# Final_Design.net
KiCad netlist of a schematic drawn in Altium Designer
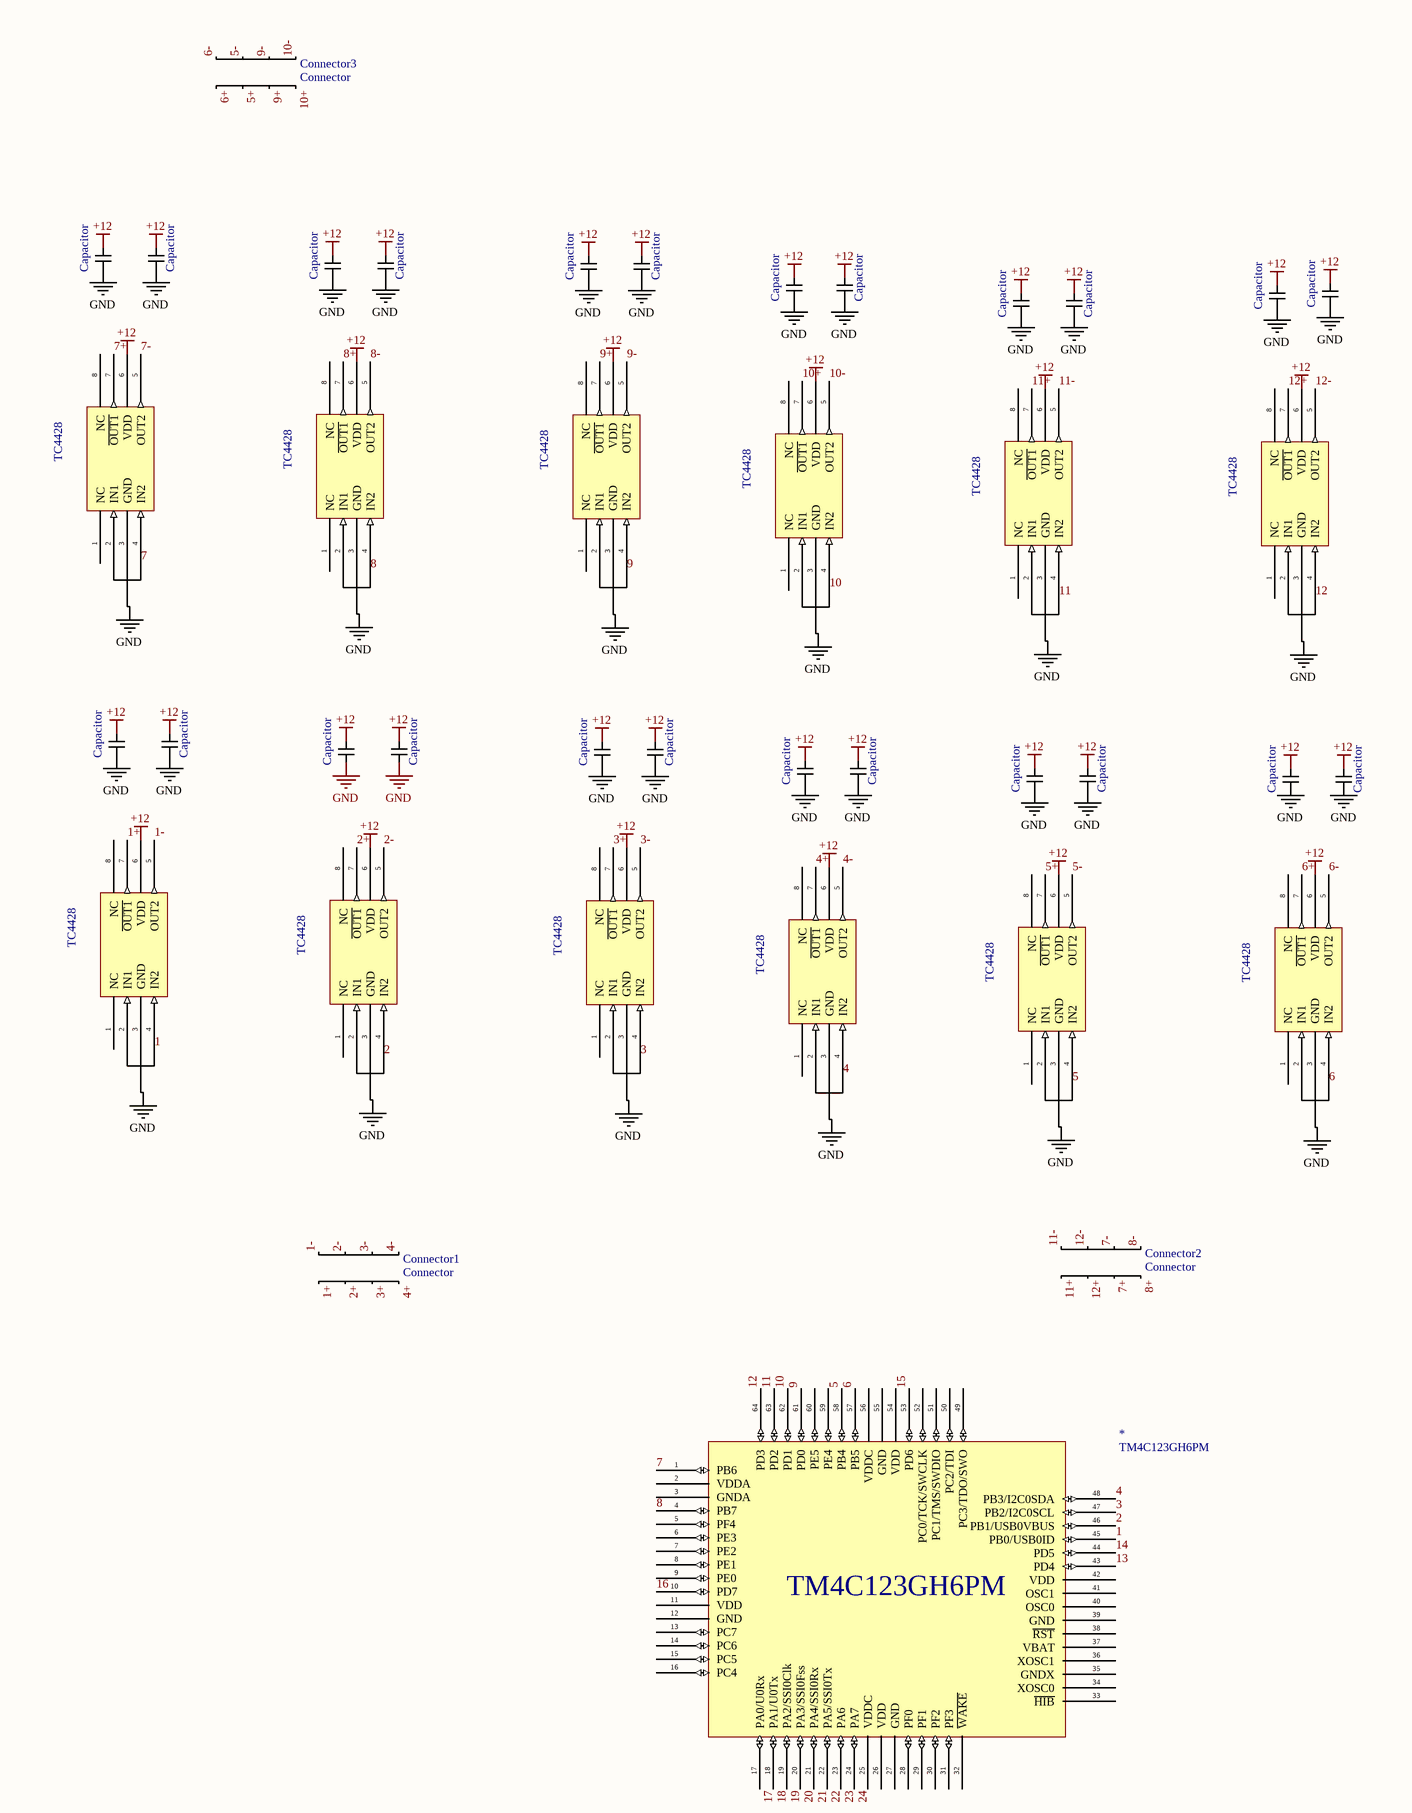
[diagram p0: Final Design.SchDoc, top]
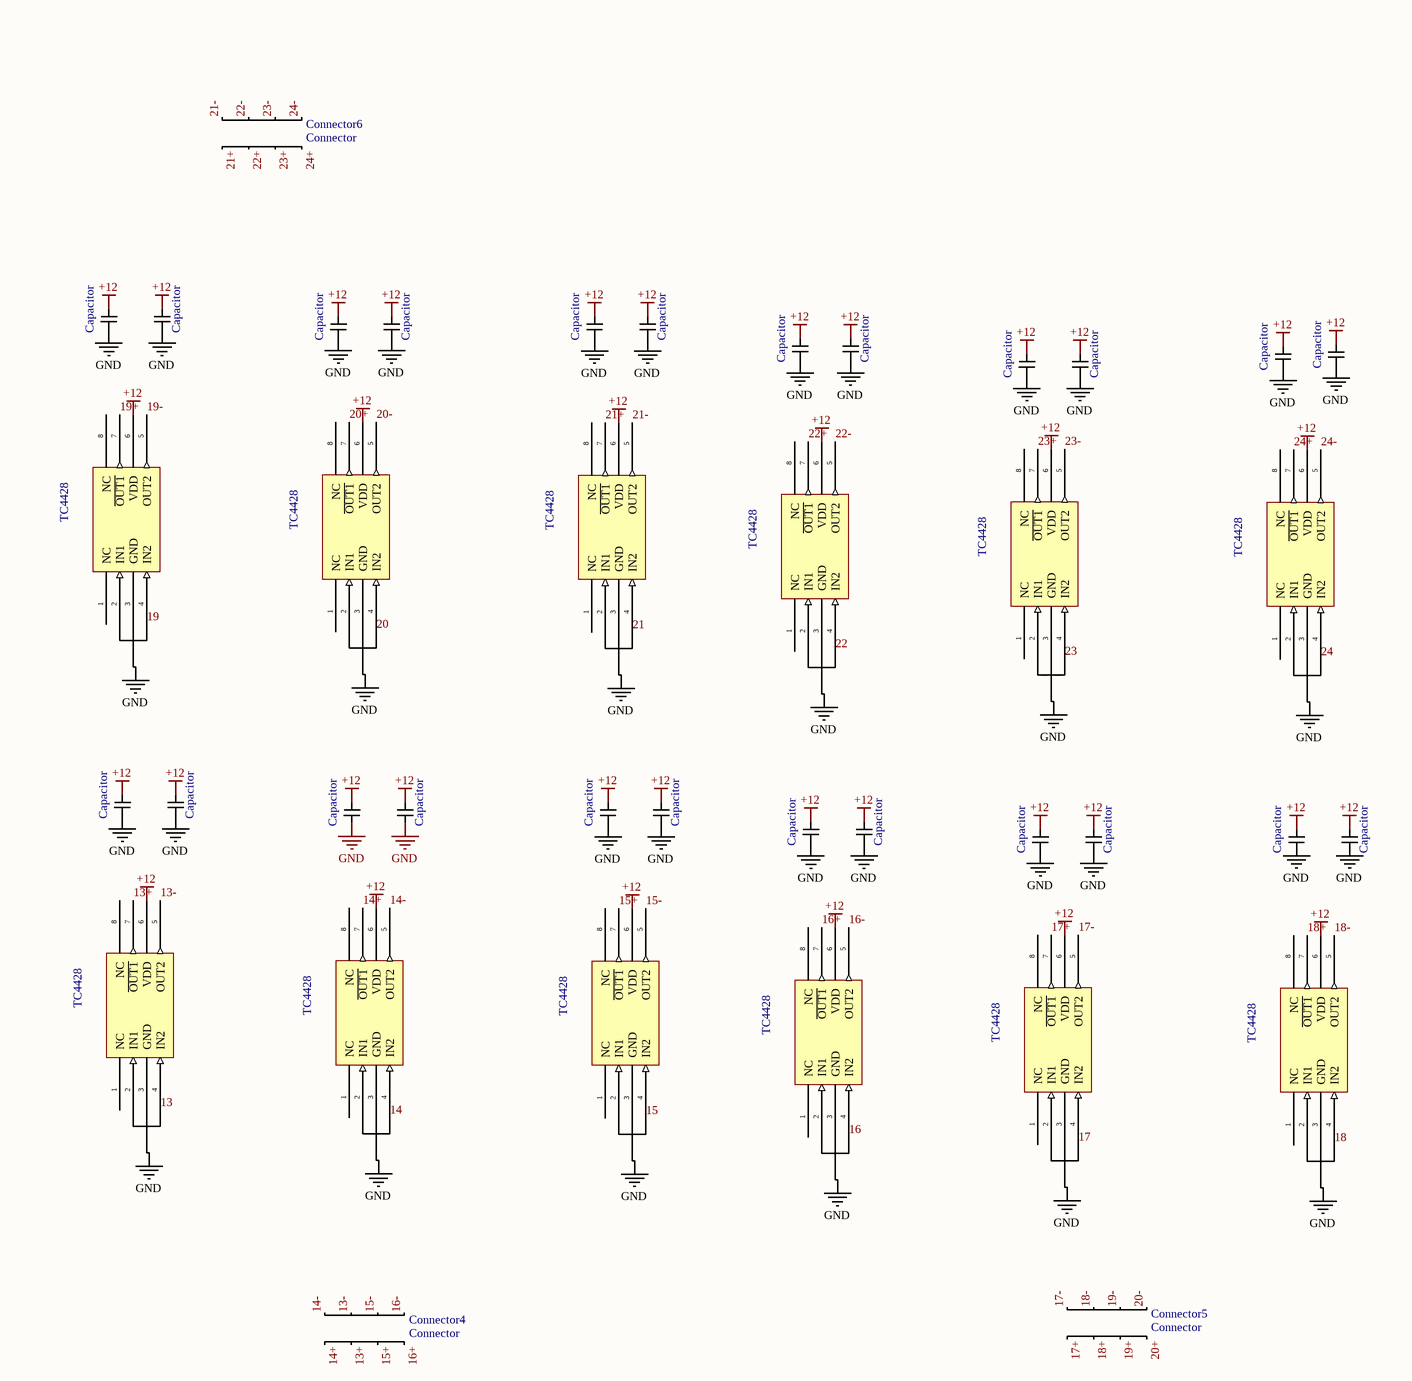
[diagram p1: Final Design.SchDoc, bottom]

(export (version "E")
  (design (tool "Eeschema 10.0.6"))
  (components
    (comp (ref "*")
      (value "TM4C123GH6PM")
      (footprint "TM4C123")
      (description "IC MCU 32BIT 256KB FLASH 64LQFP")
      (libsource (lib "Schlib1") (part "TM4C123GH6PM"))
    )
    (comp (ref "1")
      (value "TC4428")
      (footprint "TC4428")
      (description "Dual High-Speed Power MOSFET Drivers")
      (libsource (lib "Schlib1") (part "TC4428"))
    )
    (comp (ref "1.1")
      (value "Capacitor")
      (footprint "Chip2PinSM127P600-8N")
      (libsource (lib "Schlib1") (part "Capacitor"))
    )
    (comp (ref "1.2")
      (value "Capacitor")
      (footprint "Chip2PinSM127P600-8N")
      (libsource (lib "Schlib1") (part "Capacitor"))
    )
    (comp (ref "2")
      (value "TC4428")
      (footprint "TC4428")
      (description "Dual High-Speed Power MOSFET Drivers")
      (libsource (lib "Schlib1") (part "TC4428"))
    )
    (comp (ref "2.1")
      (value "Capacitor")
      (footprint "Chip2PinSM127P600-8N")
      (libsource (lib "Schlib1") (part "Capacitor"))
    )
    (comp (ref "2.2")
      (value "Capacitor")
      (footprint "Chip2PinSM127P600-8N")
      (libsource (lib "Schlib1") (part "Capacitor"))
    )
    (comp (ref "3")
      (value "TC4428")
      (footprint "TC4428")
      (description "Dual High-Speed Power MOSFET Drivers")
      (libsource (lib "Schlib1") (part "TC4428"))
    )
    (comp (ref "3.1")
      (value "Capacitor")
      (footprint "Chip2PinSM127P600-8N")
      (libsource (lib "Schlib1") (part "Capacitor"))
    )
    (comp (ref "3.2")
      (value "Capacitor")
      (footprint "Chip2PinSM127P600-8N")
      (libsource (lib "Schlib1") (part "Capacitor"))
    )
    (comp (ref "4")
      (value "TC4428")
      (footprint "TC4428")
      (description "Dual High-Speed Power MOSFET Drivers")
      (libsource (lib "Schlib1") (part "TC4428"))
    )
    (comp (ref "4.1")
      (value "Capacitor")
      (footprint "Chip2PinSM127P600-8N")
      (libsource (lib "Schlib1") (part "Capacitor"))
    )
    (comp (ref "4.2")
      (value "Capacitor")
      (footprint "Chip2PinSM127P600-8N")
      (libsource (lib "Schlib1") (part "Capacitor"))
    )
    (comp (ref "5")
      (value "TC4428")
      (footprint "TC4428")
      (description "Dual High-Speed Power MOSFET Drivers")
      (libsource (lib "Schlib1") (part "TC4428"))
    )
    (comp (ref "5.1")
      (value "Capacitor")
      (footprint "Chip2PinSM127P600-8N")
      (libsource (lib "Schlib1") (part "Capacitor"))
    )
    (comp (ref "5.2")
      (value "Capacitor")
      (footprint "Chip2PinSM127P600-8N")
      (libsource (lib "Schlib1") (part "Capacitor"))
    )
    (comp (ref "6")
      (value "TC4428")
      (footprint "TC4428")
      (description "Dual High-Speed Power MOSFET Drivers")
      (libsource (lib "Schlib1") (part "TC4428"))
    )
    (comp (ref "6.1")
      (value "Capacitor")
      (footprint "Chip2PinSM127P600-8N")
      (libsource (lib "Schlib1") (part "Capacitor"))
    )
    (comp (ref "6.2")
      (value "Capacitor")
      (footprint "Chip2PinSM127P600-8N")
      (libsource (lib "Schlib1") (part "Capacitor"))
    )
    (comp (ref "7")
      (value "TC4428")
      (footprint "TC4428")
      (description "Dual High-Speed Power MOSFET Drivers")
      (libsource (lib "Schlib1") (part "TC4428"))
    )
    (comp (ref "7.1")
      (value "Capacitor")
      (footprint "Chip2PinSM127P600-8N")
      (libsource (lib "Schlib1") (part "Capacitor"))
    )
    (comp (ref "7.2")
      (value "Capacitor")
      (footprint "Chip2PinSM127P600-8N")
      (libsource (lib "Schlib1") (part "Capacitor"))
    )
    (comp (ref "8")
      (value "TC4428")
      (footprint "TC4428")
      (description "Dual High-Speed Power MOSFET Drivers")
      (libsource (lib "Schlib1") (part "TC4428"))
    )
    (comp (ref "8.1")
      (value "Capacitor")
      (footprint "Chip2PinSM127P600-8N")
      (libsource (lib "Schlib1") (part "Capacitor"))
    )
    (comp (ref "8.2")
      (value "Capacitor")
      (footprint "Chip2PinSM127P600-8N")
      (libsource (lib "Schlib1") (part "Capacitor"))
    )
    (comp (ref "9")
      (value "TC4428")
      (footprint "TC4428")
      (description "Dual High-Speed Power MOSFET Drivers")
      (libsource (lib "Schlib1") (part "TC4428"))
    )
    (comp (ref "9.1")
      (value "Capacitor")
      (footprint "Chip2PinSM127P600-8N")
      (libsource (lib "Schlib1") (part "Capacitor"))
    )
    (comp (ref "9.2")
      (value "Capacitor")
      (footprint "Chip2PinSM127P600-8N")
      (libsource (lib "Schlib1") (part "Capacitor"))
    )
    (comp (ref "10")
      (value "TC4428")
      (footprint "TC4428")
      (description "Dual High-Speed Power MOSFET Drivers")
      (libsource (lib "Schlib1") (part "TC4428"))
    )
    (comp (ref "10.1")
      (value "Capacitor")
      (footprint "Chip2PinSM127P600-8N")
      (libsource (lib "Schlib1") (part "Capacitor"))
    )
    (comp (ref "10.2")
      (value "Capacitor")
      (footprint "Chip2PinSM127P600-8N")
      (libsource (lib "Schlib1") (part "Capacitor"))
    )
    (comp (ref "11")
      (value "TC4428")
      (footprint "TC4428")
      (description "Dual High-Speed Power MOSFET Drivers")
      (libsource (lib "Schlib1") (part "TC4428"))
    )
    (comp (ref "11.1")
      (value "Capacitor")
      (footprint "Chip2PinSM127P600-8N")
      (libsource (lib "Schlib1") (part "Capacitor"))
    )
    (comp (ref "11.2")
      (value "Capacitor")
      (footprint "Chip2PinSM127P600-8N")
      (libsource (lib "Schlib1") (part "Capacitor"))
    )
    (comp (ref "12")
      (value "TC4428")
      (footprint "TC4428")
      (description "Dual High-Speed Power MOSFET Drivers")
      (libsource (lib "Schlib1") (part "TC4428"))
    )
    (comp (ref "12.1")
      (value "Capacitor")
      (footprint "Chip2PinSM127P600-8N")
      (libsource (lib "Schlib1") (part "Capacitor"))
    )
    (comp (ref "12.2")
      (value "Capacitor")
      (footprint "Chip2PinSM127P600-8N")
      (libsource (lib "Schlib1") (part "Capacitor"))
    )
    (comp (ref "13")
      (value "TC4428")
      (footprint "TC4428")
      (description "Dual High-Speed Power MOSFET Drivers")
      (libsource (lib "Schlib1") (part "TC4428"))
    )
    (comp (ref "13.1")
      (value "Capacitor")
      (footprint "Chip2PinSM127P600-8N")
      (libsource (lib "Schlib1") (part "Capacitor"))
    )
    (comp (ref "13.2")
      (value "Capacitor")
      (footprint "Chip2PinSM127P600-8N")
      (libsource (lib "Schlib1") (part "Capacitor"))
    )
    (comp (ref "14")
      (value "TC4428")
      (footprint "TC4428")
      (description "Dual High-Speed Power MOSFET Drivers")
      (libsource (lib "Schlib1") (part "TC4428"))
    )
    (comp (ref "14.1")
      (value "Capacitor")
      (footprint "Chip2PinSM127P600-8N")
      (libsource (lib "Schlib1") (part "Capacitor"))
    )
    (comp (ref "14.2")
      (value "Capacitor")
      (footprint "Chip2PinSM127P600-8N")
      (libsource (lib "Schlib1") (part "Capacitor"))
    )
    (comp (ref "15")
      (value "TC4428")
      (footprint "TC4428")
      (description "Dual High-Speed Power MOSFET Drivers")
      (libsource (lib "Schlib1") (part "TC4428"))
    )
    (comp (ref "15.1")
      (value "Capacitor")
      (footprint "Chip2PinSM127P600-8N")
      (libsource (lib "Schlib1") (part "Capacitor"))
    )
    (comp (ref "15.2")
      (value "Capacitor")
      (footprint "Chip2PinSM127P600-8N")
      (libsource (lib "Schlib1") (part "Capacitor"))
    )
    (comp (ref "16")
      (value "TC4428")
      (footprint "TC4428")
      (description "Dual High-Speed Power MOSFET Drivers")
      (libsource (lib "Schlib1") (part "TC4428"))
    )
    (comp (ref "16.1")
      (value "Capacitor")
      (footprint "Chip2PinSM127P600-8N")
      (libsource (lib "Schlib1") (part "Capacitor"))
    )
    (comp (ref "16.2")
      (value "Capacitor")
      (footprint "Chip2PinSM127P600-8N")
      (libsource (lib "Schlib1") (part "Capacitor"))
    )
    (comp (ref "17")
      (value "TC4428")
      (footprint "TC4428")
      (description "Dual High-Speed Power MOSFET Drivers")
      (libsource (lib "Schlib1") (part "TC4428"))
    )
    (comp (ref "17+")
      (value "Capacitor")
      (footprint "Chip2PinSM127P600-8N")
      (libsource (lib "Schlib1") (part "Capacitor"))
    )
    (comp (ref "17-")
      (value "Capacitor")
      (footprint "Chip2PinSM127P600-8N")
      (libsource (lib "Schlib1") (part "Capacitor"))
    )
    (comp (ref "18")
      (value "TC4428")
      (footprint "TC4428")
      (description "Dual High-Speed Power MOSFET Drivers")
      (libsource (lib "Schlib1") (part "TC4428"))
    )
    (comp (ref "18.1")
      (value "Capacitor")
      (footprint "Chip2PinSM127P600-8N")
      (libsource (lib "Schlib1") (part "Capacitor"))
    )
    (comp (ref "18.2")
      (value "Capacitor")
      (footprint "Chip2PinSM127P600-8N")
      (libsource (lib "Schlib1") (part "Capacitor"))
    )
    (comp (ref "19")
      (value "TC4428")
      (footprint "TC4428")
      (description "Dual High-Speed Power MOSFET Drivers")
      (libsource (lib "Schlib1") (part "TC4428"))
    )
    (comp (ref "19.1")
      (value "Capacitor")
      (footprint "Chip2PinSM127P600-8N")
      (libsource (lib "Schlib1") (part "Capacitor"))
    )
    (comp (ref "19.2")
      (value "Capacitor")
      (footprint "Chip2PinSM127P600-8N")
      (libsource (lib "Schlib1") (part "Capacitor"))
    )
    (comp (ref "20")
      (value "TC4428")
      (footprint "TC4428")
      (description "Dual High-Speed Power MOSFET Drivers")
      (libsource (lib "Schlib1") (part "TC4428"))
    )
    (comp (ref "20.1")
      (value "Capacitor")
      (footprint "Chip2PinSM127P600-8N")
      (libsource (lib "Schlib1") (part "Capacitor"))
    )
    (comp (ref "20.2")
      (value "Capacitor")
      (footprint "Chip2PinSM127P600-8N")
      (libsource (lib "Schlib1") (part "Capacitor"))
    )
    (comp (ref "21")
      (value "TC4428")
      (footprint "TC4428")
      (description "Dual High-Speed Power MOSFET Drivers")
      (libsource (lib "Schlib1") (part "TC4428"))
    )
    (comp (ref "21.1")
      (value "Capacitor")
      (footprint "Chip2PinSM127P600-8N")
      (libsource (lib "Schlib1") (part "Capacitor"))
    )
    (comp (ref "21.2")
      (value "Capacitor")
      (footprint "Chip2PinSM127P600-8N")
      (libsource (lib "Schlib1") (part "Capacitor"))
    )
    (comp (ref "22")
      (value "TC4428")
      (footprint "TC4428")
      (description "Dual High-Speed Power MOSFET Drivers")
      (libsource (lib "Schlib1") (part "TC4428"))
    )
    (comp (ref "22.1")
      (value "Capacitor")
      (footprint "Chip2PinSM127P600-8N")
      (libsource (lib "Schlib1") (part "Capacitor"))
    )
    (comp (ref "22.2")
      (value "Capacitor")
      (footprint "Chip2PinSM127P600-8N")
      (libsource (lib "Schlib1") (part "Capacitor"))
    )
    (comp (ref "23")
      (value "TC4428")
      (footprint "TC4428")
      (description "Dual High-Speed Power MOSFET Drivers")
      (libsource (lib "Schlib1") (part "TC4428"))
    )
    (comp (ref "23.1")
      (value "Capacitor")
      (footprint "Chip2PinSM127P600-8N")
      (libsource (lib "Schlib1") (part "Capacitor"))
    )
    (comp (ref "23.2")
      (value "Capacitor")
      (footprint "Chip2PinSM127P600-8N")
      (libsource (lib "Schlib1") (part "Capacitor"))
    )
    (comp (ref "24")
      (value "TC4428")
      (footprint "TC4428")
      (description "Dual High-Speed Power MOSFET Drivers")
      (libsource (lib "Schlib1") (part "TC4428"))
    )
    (comp (ref "24.1")
      (value "Capacitor")
      (footprint "Chip2PinSM127P600-8N")
      (libsource (lib "Schlib1") (part "Capacitor"))
    )
    (comp (ref "24.2")
      (value "Capacitor")
      (footprint "Chip2PinSM127P600-8N")
      (libsource (lib "Schlib1") (part "Capacitor"))
    )
    (comp (ref "Connector1")
      (value "Connector")
      (footprint "Connector")
      (libsource (lib "Schlib1") (part "Connector"))
    )
    (comp (ref "Connector2")
      (value "Connector")
      (footprint "Connector")
      (libsource (lib "Schlib1") (part "Connector"))
    )
    (comp (ref "Connector3")
      (value "Connector")
      (footprint "Connector")
      (libsource (lib "Schlib1") (part "Connector"))
    )
    (comp (ref "Connector4")
      (value "Connector")
      (footprint "Connector")
      (libsource (lib "Schlib1") (part "Connector"))
    )
    (comp (ref "Connector5")
      (value "Connector")
      (footprint "Connector")
      (libsource (lib "Schlib1") (part "Connector"))
    )
    (comp (ref "Connector6")
      (value "Connector")
      (footprint "Connector")
      (libsource (lib "Schlib1") (part "Connector"))
    )
  )
  (nets
    (net (code "1") (name "+12") (class "Default")
      (node (ref "1") (pin "6") (pinfunction "VDD_6") (pintype "power_in"))
      (node (ref "1.1") (pin "pin+") (pinfunction "+_pin+") (pintype "passive"))
      (node (ref "1.2") (pin "pin+") (pinfunction "+_pin+") (pintype "passive"))
      (node (ref "10") (pin "6") (pinfunction "VDD_6") (pintype "power_in"))
      (node (ref "10.1") (pin "pin+") (pinfunction "+_pin+") (pintype "passive"))
      (node (ref "10.2") (pin "pin+") (pinfunction "+_pin+") (pintype "passive"))
      (node (ref "11") (pin "6") (pinfunction "VDD_6") (pintype "power_in"))
      (node (ref "11.1") (pin "pin+") (pinfunction "+_pin+") (pintype "passive"))
      (node (ref "11.2") (pin "pin+") (pinfunction "+_pin+") (pintype "passive"))
      (node (ref "12") (pin "6") (pinfunction "VDD_6") (pintype "power_in"))
      (node (ref "12.1") (pin "pin+") (pinfunction "+_pin+") (pintype "passive"))
      (node (ref "12.2") (pin "pin+") (pinfunction "+_pin+") (pintype "passive"))
      (node (ref "13") (pin "6") (pinfunction "VDD_6") (pintype "power_in"))
      (node (ref "13.1") (pin "pin+") (pinfunction "+_pin+") (pintype "passive"))
      (node (ref "13.2") (pin "pin+") (pinfunction "+_pin+") (pintype "passive"))
      (node (ref "14") (pin "6") (pinfunction "VDD_6") (pintype "power_in"))
      (node (ref "14.1") (pin "pin+") (pinfunction "+_pin+") (pintype "passive"))
      (node (ref "14.2") (pin "pin+") (pinfunction "+_pin+") (pintype "passive"))
      (node (ref "15") (pin "6") (pinfunction "VDD_6") (pintype "power_in"))
      (node (ref "15.1") (pin "pin+") (pinfunction "+_pin+") (pintype "passive"))
      (node (ref "15.2") (pin "pin+") (pinfunction "+_pin+") (pintype "passive"))
      (node (ref "16") (pin "6") (pinfunction "VDD_6") (pintype "power_in"))
      (node (ref "16.1") (pin "pin+") (pinfunction "+_pin+") (pintype "passive"))
      (node (ref "16.2") (pin "pin+") (pinfunction "+_pin+") (pintype "passive"))
      (node (ref "17") (pin "6") (pinfunction "VDD_6") (pintype "power_in"))
      (node (ref "17+") (pin "pin+") (pinfunction "+_pin+") (pintype "passive"))
      (node (ref "17-") (pin "pin+") (pinfunction "+_pin+") (pintype "passive"))
      (node (ref "18") (pin "6") (pinfunction "VDD_6") (pintype "power_in"))
      (node (ref "18.1") (pin "pin+") (pinfunction "+_pin+") (pintype "passive"))
      (node (ref "18.2") (pin "pin+") (pinfunction "+_pin+") (pintype "passive"))
      (node (ref "19") (pin "6") (pinfunction "VDD_6") (pintype "power_in"))
      (node (ref "19.1") (pin "pin+") (pinfunction "+_pin+") (pintype "passive"))
      (node (ref "19.2") (pin "pin+") (pinfunction "+_pin+") (pintype "passive"))
      (node (ref "2") (pin "6") (pinfunction "VDD_6") (pintype "power_in"))
      (node (ref "2.1") (pin "pin+") (pinfunction "+_pin+") (pintype "passive"))
      (node (ref "2.2") (pin "pin+") (pinfunction "+_pin+") (pintype "passive"))
      (node (ref "20") (pin "6") (pinfunction "VDD_6") (pintype "power_in"))
      (node (ref "20.1") (pin "pin+") (pinfunction "+_pin+") (pintype "passive"))
      (node (ref "20.2") (pin "pin+") (pinfunction "+_pin+") (pintype "passive"))
      (node (ref "21") (pin "6") (pinfunction "VDD_6") (pintype "power_in"))
      (node (ref "21.1") (pin "pin+") (pinfunction "+_pin+") (pintype "passive"))
      (node (ref "21.2") (pin "pin+") (pinfunction "+_pin+") (pintype "passive"))
      (node (ref "22") (pin "6") (pinfunction "VDD_6") (pintype "power_in"))
      (node (ref "22.1") (pin "pin+") (pinfunction "+_pin+") (pintype "passive"))
      (node (ref "22.2") (pin "pin+") (pinfunction "+_pin+") (pintype "passive"))
      (node (ref "23") (pin "6") (pinfunction "VDD_6") (pintype "power_in"))
      (node (ref "23.1") (pin "pin+") (pinfunction "+_pin+") (pintype "passive"))
      (node (ref "23.2") (pin "pin+") (pinfunction "+_pin+") (pintype "passive"))
      (node (ref "24") (pin "6") (pinfunction "VDD_6") (pintype "power_in"))
      (node (ref "24.1") (pin "pin+") (pinfunction "+_pin+") (pintype "passive"))
      (node (ref "24.2") (pin "pin+") (pinfunction "+_pin+") (pintype "passive"))
      (node (ref "3") (pin "6") (pinfunction "VDD_6") (pintype "power_in"))
      (node (ref "3.1") (pin "pin+") (pinfunction "+_pin+") (pintype "passive"))
      (node (ref "3.2") (pin "pin+") (pinfunction "+_pin+") (pintype "passive"))
      (node (ref "4") (pin "6") (pinfunction "VDD_6") (pintype "power_in"))
      (node (ref "4.1") (pin "pin+") (pinfunction "+_pin+") (pintype "passive"))
      (node (ref "4.2") (pin "pin+") (pinfunction "+_pin+") (pintype "passive"))
      (node (ref "5") (pin "6") (pinfunction "VDD_6") (pintype "power_in"))
      (node (ref "5.1") (pin "pin+") (pinfunction "+_pin+") (pintype "passive"))
      (node (ref "5.2") (pin "pin+") (pinfunction "+_pin+") (pintype "passive"))
      (node (ref "6") (pin "6") (pinfunction "VDD_6") (pintype "power_in"))
      (node (ref "6.1") (pin "pin+") (pinfunction "+_pin+") (pintype "passive"))
      (node (ref "6.2") (pin "pin+") (pinfunction "+_pin+") (pintype "passive"))
      (node (ref "7") (pin "6") (pinfunction "VDD_6") (pintype "power_in"))
      (node (ref "7.1") (pin "pin+") (pinfunction "+_pin+") (pintype "passive"))
      (node (ref "7.2") (pin "pin+") (pinfunction "+_pin+") (pintype "passive"))
      (node (ref "8") (pin "6") (pinfunction "VDD_6") (pintype "power_in"))
      (node (ref "8.1") (pin "pin+") (pinfunction "+_pin+") (pintype "passive"))
      (node (ref "8.2") (pin "pin+") (pinfunction "+_pin+") (pintype "passive"))
      (node (ref "9") (pin "6") (pinfunction "VDD_6") (pintype "power_in"))
      (node (ref "9.1") (pin "pin+") (pinfunction "+_pin+") (pintype "passive"))
      (node (ref "9.2") (pin "pin+") (pinfunction "+_pin+") (pintype "passive"))
    )
    (net (code "2") (name "/1") (class "Default")
      (node (ref "*") (pin "45") (pinfunction "PB0/USB0ID_45") (pintype "bidirectional"))
      (node (ref "1") (pin "2") (pinfunction "IN1_2") (pintype "input"))
      (node (ref "1") (pin "4") (pinfunction "IN2_4") (pintype "input"))
    )
    (net (code "3") (name "/1+") (class "Default")
      (node (ref "1") (pin "7") (pinfunction "~{OUT1}_7") (pintype "output"))
      (node (ref "Connector1") (pin "1") (pinfunction "1_1") (pintype "passive"))
    )
    (net (code "4") (name "/1-") (class "Default")
      (node (ref "1") (pin "5") (pinfunction "OUT2_5") (pintype "output"))
      (node (ref "Connector1") (pin "8") (pinfunction "8_8") (pintype "passive"))
    )
    (net (code "5") (name "/2") (class "Default")
      (node (ref "*") (pin "46") (pinfunction "PB1/USB0VBUS_46") (pintype "bidirectional"))
      (node (ref "2") (pin "2") (pinfunction "IN1_2") (pintype "input"))
      (node (ref "2") (pin "4") (pinfunction "IN2_4") (pintype "input"))
    )
    (net (code "6") (name "/2+") (class "Default")
      (node (ref "2") (pin "7") (pinfunction "~{OUT1}_7") (pintype "output"))
      (node (ref "Connector1") (pin "2") (pinfunction "2_2") (pintype "passive"))
    )
    (net (code "7") (name "/2-") (class "Default")
      (node (ref "2") (pin "5") (pinfunction "OUT2_5") (pintype "output"))
      (node (ref "Connector1") (pin "7") (pinfunction "7_7") (pintype "passive"))
    )
    (net (code "8") (name "/3") (class "Default")
      (node (ref "*") (pin "47") (pinfunction "PB2/I2C0SCL_47") (pintype "bidirectional"))
      (node (ref "3") (pin "2") (pinfunction "IN1_2") (pintype "input"))
      (node (ref "3") (pin "4") (pinfunction "IN2_4") (pintype "input"))
    )
    (net (code "9") (name "/3+") (class "Default")
      (node (ref "3") (pin "7") (pinfunction "~{OUT1}_7") (pintype "output"))
      (node (ref "Connector1") (pin "3") (pinfunction "3_3") (pintype "passive"))
    )
    (net (code "10") (name "/3-") (class "Default")
      (node (ref "3") (pin "5") (pinfunction "OUT2_5") (pintype "output"))
      (node (ref "Connector1") (pin "6") (pinfunction "6_6") (pintype "passive"))
    )
    (net (code "11") (name "/4") (class "Default")
      (node (ref "*") (pin "48") (pinfunction "PB3/I2C0SDA_48") (pintype "bidirectional"))
      (node (ref "4") (pin "2") (pinfunction "IN1_2") (pintype "input"))
      (node (ref "4") (pin "4") (pinfunction "IN2_4") (pintype "input"))
    )
    (net (code "12") (name "/4+") (class "Default")
      (node (ref "4") (pin "7") (pinfunction "~{OUT1}_7") (pintype "output"))
      (node (ref "Connector1") (pin "4") (pinfunction "4_4") (pintype "passive"))
    )
    (net (code "13") (name "/4-") (class "Default")
      (node (ref "4") (pin "5") (pinfunction "OUT2_5") (pintype "output"))
      (node (ref "Connector1") (pin "5") (pinfunction "5_5") (pintype "passive"))
    )
    (net (code "14") (name "/5") (class "Default")
      (node (ref "*") (pin "58") (pinfunction "PB4_58") (pintype "bidirectional"))
      (node (ref "5") (pin "2") (pinfunction "IN1_2") (pintype "input"))
      (node (ref "5") (pin "4") (pinfunction "IN2_4") (pintype "input"))
    )
    (net (code "15") (name "/5+") (class "Default")
      (node (ref "5") (pin "7") (pinfunction "~{OUT1}_7") (pintype "output"))
      (node (ref "Connector3") (pin "2") (pinfunction "2_2") (pintype "passive"))
    )
    (net (code "16") (name "/5-") (class "Default")
      (node (ref "5") (pin "5") (pinfunction "OUT2_5") (pintype "output"))
      (node (ref "Connector3") (pin "7") (pinfunction "7_7") (pintype "passive"))
    )
    (net (code "17") (name "/6") (class "Default")
      (node (ref "*") (pin "57") (pinfunction "PB5_57") (pintype "bidirectional"))
      (node (ref "6") (pin "2") (pinfunction "IN1_2") (pintype "input"))
      (node (ref "6") (pin "4") (pinfunction "IN2_4") (pintype "input"))
    )
    (net (code "18") (name "/6+") (class "Default")
      (node (ref "6") (pin "7") (pinfunction "~{OUT1}_7") (pintype "output"))
      (node (ref "Connector3") (pin "1") (pinfunction "1_1") (pintype "passive"))
    )
    (net (code "19") (name "/6-") (class "Default")
      (node (ref "6") (pin "5") (pinfunction "OUT2_5") (pintype "output"))
      (node (ref "Connector3") (pin "8") (pinfunction "8_8") (pintype "passive"))
    )
    (net (code "20") (name "/7") (class "Default")
      (node (ref "*") (pin "1") (pinfunction "PB6_1") (pintype "bidirectional"))
      (node (ref "7") (pin "2") (pinfunction "IN1_2") (pintype "input"))
      (node (ref "7") (pin "4") (pinfunction "IN2_4") (pintype "input"))
    )
    (net (code "21") (name "/7+") (class "Default")
      (node (ref "7") (pin "7") (pinfunction "~{OUT1}_7") (pintype "output"))
      (node (ref "Connector2") (pin "3") (pinfunction "3_3") (pintype "passive"))
    )
    (net (code "22") (name "/7-") (class "Default")
      (node (ref "7") (pin "5") (pinfunction "OUT2_5") (pintype "output"))
      (node (ref "Connector2") (pin "6") (pinfunction "6_6") (pintype "passive"))
    )
    (net (code "23") (name "/8") (class "Default")
      (node (ref "*") (pin "4") (pinfunction "PB7_4") (pintype "bidirectional"))
      (node (ref "8") (pin "2") (pinfunction "IN1_2") (pintype "input"))
      (node (ref "8") (pin "4") (pinfunction "IN2_4") (pintype "input"))
    )
    (net (code "24") (name "/8+") (class "Default")
      (node (ref "8") (pin "7") (pinfunction "~{OUT1}_7") (pintype "output"))
      (node (ref "Connector2") (pin "4") (pinfunction "4_4") (pintype "passive"))
    )
    (net (code "25") (name "/8-") (class "Default")
      (node (ref "8") (pin "5") (pinfunction "OUT2_5") (pintype "output"))
      (node (ref "Connector2") (pin "5") (pinfunction "5_5") (pintype "passive"))
    )
    (net (code "26") (name "/9") (class "Default")
      (node (ref "*") (pin "61") (pinfunction "PD0_61") (pintype "bidirectional"))
      (node (ref "9") (pin "2") (pinfunction "IN1_2") (pintype "input"))
      (node (ref "9") (pin "4") (pinfunction "IN2_4") (pintype "input"))
    )
    (net (code "27") (name "/9+") (class "Default")
      (node (ref "9") (pin "7") (pinfunction "~{OUT1}_7") (pintype "output"))
      (node (ref "Connector3") (pin "3") (pinfunction "3_3") (pintype "passive"))
    )
    (net (code "28") (name "/9-") (class "Default")
      (node (ref "9") (pin "5") (pinfunction "OUT2_5") (pintype "output"))
      (node (ref "Connector3") (pin "6") (pinfunction "6_6") (pintype "passive"))
    )
    (net (code "29") (name "/10") (class "Default")
      (node (ref "*") (pin "62") (pinfunction "PD1_62") (pintype "bidirectional"))
      (node (ref "10") (pin "2") (pinfunction "IN1_2") (pintype "input"))
      (node (ref "10") (pin "4") (pinfunction "IN2_4") (pintype "input"))
    )
    (net (code "30") (name "/10+") (class "Default")
      (node (ref "10") (pin "7") (pinfunction "~{OUT1}_7") (pintype "output"))
      (node (ref "Connector3") (pin "4") (pinfunction "4_4") (pintype "passive"))
    )
    (net (code "31") (name "/10-") (class "Default")
      (node (ref "10") (pin "5") (pinfunction "OUT2_5") (pintype "output"))
      (node (ref "Connector3") (pin "5") (pinfunction "5_5") (pintype "passive"))
    )
    (net (code "32") (name "/11") (class "Default")
      (node (ref "*") (pin "63") (pinfunction "PD2_63") (pintype "bidirectional"))
      (node (ref "11") (pin "2") (pinfunction "IN1_2") (pintype "input"))
      (node (ref "11") (pin "4") (pinfunction "IN2_4") (pintype "input"))
    )
    (net (code "33") (name "/11+") (class "Default")
      (node (ref "11") (pin "7") (pinfunction "~{OUT1}_7") (pintype "output"))
      (node (ref "Connector2") (pin "1") (pinfunction "1_1") (pintype "passive"))
    )
    (net (code "34") (name "/11-") (class "Default")
      (node (ref "11") (pin "5") (pinfunction "OUT2_5") (pintype "output"))
      (node (ref "Connector2") (pin "8") (pinfunction "8_8") (pintype "passive"))
    )
    (net (code "35") (name "/12") (class "Default")
      (node (ref "*") (pin "64") (pinfunction "PD3_64") (pintype "bidirectional"))
      (node (ref "12") (pin "2") (pinfunction "IN1_2") (pintype "input"))
      (node (ref "12") (pin "4") (pinfunction "IN2_4") (pintype "input"))
    )
    (net (code "36") (name "/12+") (class "Default")
      (node (ref "12") (pin "7") (pinfunction "~{OUT1}_7") (pintype "output"))
      (node (ref "Connector2") (pin "2") (pinfunction "2_2") (pintype "passive"))
    )
    (net (code "37") (name "/12-") (class "Default")
      (node (ref "12") (pin "5") (pinfunction "OUT2_5") (pintype "output"))
      (node (ref "Connector2") (pin "7") (pinfunction "7_7") (pintype "passive"))
    )
    (net (code "38") (name "/13") (class "Default")
      (node (ref "*") (pin "43") (pinfunction "PD4_43") (pintype "bidirectional"))
      (node (ref "13") (pin "2") (pinfunction "IN1_2") (pintype "input"))
      (node (ref "13") (pin "4") (pinfunction "IN2_4") (pintype "input"))
    )
    (net (code "39") (name "/13+") (class "Default")
      (node (ref "13") (pin "7") (pinfunction "~{OUT1}_7") (pintype "output"))
      (node (ref "Connector4") (pin "2") (pinfunction "2_2") (pintype "passive"))
    )
    (net (code "40") (name "/13-") (class "Default")
      (node (ref "13") (pin "5") (pinfunction "OUT2_5") (pintype "output"))
      (node (ref "Connector4") (pin "7") (pinfunction "7_7") (pintype "passive"))
    )
    (net (code "41") (name "/14") (class "Default")
      (node (ref "*") (pin "44") (pinfunction "PD5_44") (pintype "bidirectional"))
      (node (ref "14") (pin "2") (pinfunction "IN1_2") (pintype "input"))
      (node (ref "14") (pin "4") (pinfunction "IN2_4") (pintype "input"))
    )
    (net (code "42") (name "/14+") (class "Default")
      (node (ref "14") (pin "7") (pinfunction "~{OUT1}_7") (pintype "output"))
      (node (ref "Connector4") (pin "1") (pinfunction "1_1") (pintype "passive"))
    )
    (net (code "43") (name "/14-") (class "Default")
      (node (ref "14") (pin "5") (pinfunction "OUT2_5") (pintype "output"))
      (node (ref "Connector4") (pin "8") (pinfunction "8_8") (pintype "passive"))
    )
    (net (code "44") (name "/15") (class "Default")
      (node (ref "*") (pin "53") (pinfunction "PD6_53") (pintype "bidirectional"))
      (node (ref "15") (pin "2") (pinfunction "IN1_2") (pintype "input"))
      (node (ref "15") (pin "4") (pinfunction "IN2_4") (pintype "input"))
    )
    (net (code "45") (name "/15+") (class "Default")
      (node (ref "15") (pin "7") (pinfunction "~{OUT1}_7") (pintype "output"))
      (node (ref "Connector4") (pin "3") (pinfunction "3_3") (pintype "passive"))
    )
    (net (code "46") (name "/15-") (class "Default")
      (node (ref "15") (pin "5") (pinfunction "OUT2_5") (pintype "output"))
      (node (ref "Connector4") (pin "6") (pinfunction "6_6") (pintype "passive"))
    )
    (net (code "47") (name "/16") (class "Default")
      (node (ref "*") (pin "10") (pinfunction "PD7_10") (pintype "bidirectional"))
      (node (ref "16") (pin "2") (pinfunction "IN1_2") (pintype "input"))
      (node (ref "16") (pin "4") (pinfunction "IN2_4") (pintype "input"))
    )
    (net (code "48") (name "/16+") (class "Default")
      (node (ref "16") (pin "7") (pinfunction "~{OUT1}_7") (pintype "output"))
      (node (ref "Connector4") (pin "4") (pinfunction "4_4") (pintype "passive"))
    )
    (net (code "49") (name "/16-") (class "Default")
      (node (ref "16") (pin "5") (pinfunction "OUT2_5") (pintype "output"))
      (node (ref "Connector4") (pin "5") (pinfunction "5_5") (pintype "passive"))
    )
    (net (code "50") (name "/17") (class "Default")
      (node (ref "*") (pin "17") (pinfunction "PA0/U0Rx_17") (pintype "bidirectional"))
      (node (ref "17") (pin "2") (pinfunction "IN1_2") (pintype "input"))
      (node (ref "17") (pin "4") (pinfunction "IN2_4") (pintype "input"))
    )
    (net (code "51") (name "/17+") (class "Default")
      (node (ref "17") (pin "7") (pinfunction "~{OUT1}_7") (pintype "output"))
      (node (ref "Connector5") (pin "1") (pinfunction "1_1") (pintype "passive"))
    )
    (net (code "52") (name "/17-") (class "Default")
      (node (ref "17") (pin "5") (pinfunction "OUT2_5") (pintype "output"))
      (node (ref "Connector5") (pin "8") (pinfunction "8_8") (pintype "passive"))
    )
    (net (code "53") (name "/18") (class "Default")
      (node (ref "*") (pin "18") (pinfunction "PA1/U0Tx_18") (pintype "bidirectional"))
      (node (ref "18") (pin "2") (pinfunction "IN1_2") (pintype "input"))
      (node (ref "18") (pin "4") (pinfunction "IN2_4") (pintype "input"))
    )
    (net (code "54") (name "/18+") (class "Default")
      (node (ref "18") (pin "7") (pinfunction "~{OUT1}_7") (pintype "output"))
      (node (ref "Connector5") (pin "2") (pinfunction "2_2") (pintype "passive"))
    )
    (net (code "55") (name "/18-") (class "Default")
      (node (ref "18") (pin "5") (pinfunction "OUT2_5") (pintype "output"))
      (node (ref "Connector5") (pin "7") (pinfunction "7_7") (pintype "passive"))
    )
    (net (code "56") (name "/19") (class "Default")
      (node (ref "*") (pin "19") (pinfunction "PA2/SSI0Clk_19") (pintype "bidirectional"))
      (node (ref "19") (pin "2") (pinfunction "IN1_2") (pintype "input"))
      (node (ref "19") (pin "4") (pinfunction "IN2_4") (pintype "input"))
    )
    (net (code "57") (name "/19+") (class "Default")
      (node (ref "19") (pin "7") (pinfunction "~{OUT1}_7") (pintype "output"))
      (node (ref "Connector5") (pin "3") (pinfunction "3_3") (pintype "passive"))
    )
    (net (code "58") (name "/19-") (class "Default")
      (node (ref "19") (pin "5") (pinfunction "OUT2_5") (pintype "output"))
      (node (ref "Connector5") (pin "6") (pinfunction "6_6") (pintype "passive"))
    )
    (net (code "59") (name "/20") (class "Default")
      (node (ref "*") (pin "20") (pinfunction "PA3/SSI0Fss_20") (pintype "bidirectional"))
      (node (ref "20") (pin "2") (pinfunction "IN1_2") (pintype "input"))
      (node (ref "20") (pin "4") (pinfunction "IN2_4") (pintype "input"))
    )
    (net (code "60") (name "/20+") (class "Default")
      (node (ref "20") (pin "7") (pinfunction "~{OUT1}_7") (pintype "output"))
      (node (ref "Connector5") (pin "4") (pinfunction "4_4") (pintype "passive"))
    )
    (net (code "61") (name "/20-") (class "Default")
      (node (ref "20") (pin "5") (pinfunction "OUT2_5") (pintype "output"))
      (node (ref "Connector5") (pin "5") (pinfunction "5_5") (pintype "passive"))
    )
    (net (code "62") (name "/21") (class "Default")
      (node (ref "*") (pin "21") (pinfunction "PA4/SSI0Rx_21") (pintype "bidirectional"))
      (node (ref "21") (pin "2") (pinfunction "IN1_2") (pintype "input"))
      (node (ref "21") (pin "4") (pinfunction "IN2_4") (pintype "input"))
    )
    (net (code "63") (name "/21+") (class "Default")
      (node (ref "21") (pin "7") (pinfunction "~{OUT1}_7") (pintype "output"))
      (node (ref "Connector6") (pin "1") (pinfunction "1_1") (pintype "passive"))
    )
    (net (code "64") (name "/21-") (class "Default")
      (node (ref "21") (pin "5") (pinfunction "OUT2_5") (pintype "output"))
      (node (ref "Connector6") (pin "8") (pinfunction "8_8") (pintype "passive"))
    )
    (net (code "65") (name "/22") (class "Default")
      (node (ref "*") (pin "22") (pinfunction "PA5/SSI0Tx_22") (pintype "bidirectional"))
      (node (ref "22") (pin "2") (pinfunction "IN1_2") (pintype "input"))
      (node (ref "22") (pin "4") (pinfunction "IN2_4") (pintype "input"))
    )
    (net (code "66") (name "/22+") (class "Default")
      (node (ref "22") (pin "7") (pinfunction "~{OUT1}_7") (pintype "output"))
      (node (ref "Connector6") (pin "2") (pinfunction "2_2") (pintype "passive"))
    )
    (net (code "67") (name "/22-") (class "Default")
      (node (ref "22") (pin "5") (pinfunction "OUT2_5") (pintype "output"))
      (node (ref "Connector6") (pin "7") (pinfunction "7_7") (pintype "passive"))
    )
    (net (code "68") (name "/23") (class "Default")
      (node (ref "*") (pin "23") (pinfunction "PA6_23") (pintype "bidirectional"))
      (node (ref "23") (pin "2") (pinfunction "IN1_2") (pintype "input"))
      (node (ref "23") (pin "4") (pinfunction "IN2_4") (pintype "input"))
    )
    (net (code "69") (name "/23+") (class "Default")
      (node (ref "23") (pin "7") (pinfunction "~{OUT1}_7") (pintype "output"))
      (node (ref "Connector6") (pin "3") (pinfunction "3_3") (pintype "passive"))
    )
    (net (code "70") (name "/23-") (class "Default")
      (node (ref "23") (pin "5") (pinfunction "OUT2_5") (pintype "output"))
      (node (ref "Connector6") (pin "6") (pinfunction "6_6") (pintype "passive"))
    )
    (net (code "71") (name "/24") (class "Default")
      (node (ref "*") (pin "24") (pinfunction "PA7_24") (pintype "bidirectional"))
      (node (ref "24") (pin "2") (pinfunction "IN1_2") (pintype "input"))
      (node (ref "24") (pin "4") (pinfunction "IN2_4") (pintype "input"))
    )
    (net (code "72") (name "/24+") (class "Default")
      (node (ref "24") (pin "7") (pinfunction "~{OUT1}_7") (pintype "output"))
      (node (ref "Connector6") (pin "4") (pinfunction "4_4") (pintype "passive"))
    )
    (net (code "73") (name "/24-") (class "Default")
      (node (ref "24") (pin "5") (pinfunction "OUT2_5") (pintype "output"))
      (node (ref "Connector6") (pin "5") (pinfunction "5_5") (pintype "passive"))
    )
    (net (code "75") (name "GND") (class "Default")
      (node (ref "1") (pin "3") (pinfunction "GND_3") (pintype "power_in"))
      (node (ref "1.1") (pin "pin-") (pinfunction "-_pin-") (pintype "passive"))
      (node (ref "1.2") (pin "pin-") (pinfunction "-_pin-") (pintype "passive"))
      (node (ref "10") (pin "3") (pinfunction "GND_3") (pintype "power_in"))
      (node (ref "10.1") (pin "pin-") (pinfunction "-_pin-") (pintype "passive"))
      (node (ref "10.2") (pin "pin-") (pinfunction "-_pin-") (pintype "passive"))
      (node (ref "11") (pin "3") (pinfunction "GND_3") (pintype "power_in"))
      (node (ref "11.1") (pin "pin-") (pinfunction "-_pin-") (pintype "passive"))
      (node (ref "11.2") (pin "pin-") (pinfunction "-_pin-") (pintype "passive"))
      (node (ref "12") (pin "3") (pinfunction "GND_3") (pintype "power_in"))
      (node (ref "12.1") (pin "pin-") (pinfunction "-_pin-") (pintype "passive"))
      (node (ref "13") (pin "3") (pinfunction "GND_3") (pintype "power_in"))
      (node (ref "13.1") (pin "pin-") (pinfunction "-_pin-") (pintype "passive"))
      (node (ref "13.2") (pin "pin-") (pinfunction "-_pin-") (pintype "passive"))
      (node (ref "14") (pin "3") (pinfunction "GND_3") (pintype "power_in"))
      (node (ref "14.1") (pin "pin-") (pinfunction "-_pin-") (pintype "passive"))
      (node (ref "14.2") (pin "pin-") (pinfunction "-_pin-") (pintype "passive"))
      (node (ref "15") (pin "3") (pinfunction "GND_3") (pintype "power_in"))
      (node (ref "15.1") (pin "pin-") (pinfunction "-_pin-") (pintype "passive"))
      (node (ref "15.2") (pin "pin-") (pinfunction "-_pin-") (pintype "passive"))
      (node (ref "16") (pin "3") (pinfunction "GND_3") (pintype "power_in"))
      (node (ref "16.1") (pin "pin-") (pinfunction "-_pin-") (pintype "passive"))
      (node (ref "16.2") (pin "pin-") (pinfunction "-_pin-") (pintype "passive"))
      (node (ref "17") (pin "3") (pinfunction "GND_3") (pintype "power_in"))
      (node (ref "17+") (pin "pin-") (pinfunction "-_pin-") (pintype "passive"))
      (node (ref "17-") (pin "pin-") (pinfunction "-_pin-") (pintype "passive"))
      (node (ref "18") (pin "3") (pinfunction "GND_3") (pintype "power_in"))
      (node (ref "19") (pin "3") (pinfunction "GND_3") (pintype "power_in"))
      (node (ref "19.1") (pin "pin-") (pinfunction "-_pin-") (pintype "passive"))
      (node (ref "19.2") (pin "pin-") (pinfunction "-_pin-") (pintype "passive"))
      (node (ref "2") (pin "3") (pinfunction "GND_3") (pintype "power_in"))
      (node (ref "2.1") (pin "pin-") (pinfunction "-_pin-") (pintype "passive"))
      (node (ref "2.2") (pin "pin-") (pinfunction "-_pin-") (pintype "passive"))
      (node (ref "20") (pin "3") (pinfunction "GND_3") (pintype "power_in"))
      (node (ref "20.1") (pin "pin-") (pinfunction "-_pin-") (pintype "passive"))
      (node (ref "20.2") (pin "pin-") (pinfunction "-_pin-") (pintype "passive"))
      (node (ref "21") (pin "3") (pinfunction "GND_3") (pintype "power_in"))
      (node (ref "21.1") (pin "pin-") (pinfunction "-_pin-") (pintype "passive"))
      (node (ref "21.2") (pin "pin-") (pinfunction "-_pin-") (pintype "passive"))
      (node (ref "22") (pin "3") (pinfunction "GND_3") (pintype "power_in"))
      (node (ref "22.1") (pin "pin-") (pinfunction "-_pin-") (pintype "passive"))
      (node (ref "22.2") (pin "pin-") (pinfunction "-_pin-") (pintype "passive"))
      (node (ref "23") (pin "3") (pinfunction "GND_3") (pintype "power_in"))
      (node (ref "23.1") (pin "pin-") (pinfunction "-_pin-") (pintype "passive"))
      (node (ref "23.2") (pin "pin-") (pinfunction "-_pin-") (pintype "passive"))
      (node (ref "24") (pin "3") (pinfunction "GND_3") (pintype "power_in"))
      (node (ref "24.1") (pin "pin-") (pinfunction "-_pin-") (pintype "passive"))
      (node (ref "3") (pin "3") (pinfunction "GND_3") (pintype "power_in"))
      (node (ref "3.1") (pin "pin-") (pinfunction "-_pin-") (pintype "passive"))
      (node (ref "3.2") (pin "pin-") (pinfunction "-_pin-") (pintype "passive"))
      (node (ref "4") (pin "3") (pinfunction "GND_3") (pintype "power_in"))
      (node (ref "4.1") (pin "pin-") (pinfunction "-_pin-") (pintype "passive"))
      (node (ref "4.2") (pin "pin-") (pinfunction "-_pin-") (pintype "passive"))
      (node (ref "5") (pin "3") (pinfunction "GND_3") (pintype "power_in"))
      (node (ref "5.1") (pin "pin-") (pinfunction "-_pin-") (pintype "passive"))
      (node (ref "5.2") (pin "pin-") (pinfunction "-_pin-") (pintype "passive"))
      (node (ref "6") (pin "3") (pinfunction "GND_3") (pintype "power_in"))
      (node (ref "7") (pin "3") (pinfunction "GND_3") (pintype "power_in"))
      (node (ref "7.1") (pin "pin-") (pinfunction "-_pin-") (pintype "passive"))
      (node (ref "7.2") (pin "pin-") (pinfunction "-_pin-") (pintype "passive"))
      (node (ref "8") (pin "3") (pinfunction "GND_3") (pintype "power_in"))
      (node (ref "8.1") (pin "pin-") (pinfunction "-_pin-") (pintype "passive"))
      (node (ref "8.2") (pin "pin-") (pinfunction "-_pin-") (pintype "passive"))
      (node (ref "9") (pin "3") (pinfunction "GND_3") (pintype "power_in"))
      (node (ref "9.1") (pin "pin-") (pinfunction "-_pin-") (pintype "passive"))
      (node (ref "9.2") (pin "pin-") (pinfunction "-_pin-") (pintype "passive"))
    )
    (net (code "76") (name "unconnected-(*-GND-Pad12)") (class "Default")
      (node (ref "*") (pin "12") (pinfunction "GND_12") (pintype "power_in"))
    )
    (net (code "77") (name "unconnected-(*-GND-Pad27)") (class "Default")
      (node (ref "*") (pin "27") (pinfunction "GND_27") (pintype "power_in"))
    )
    (net (code "78") (name "unconnected-(*-GND-Pad39)") (class "Default")
      (node (ref "*") (pin "39") (pinfunction "GND_39") (pintype "power_in"))
    )
    (net (code "79") (name "unconnected-(*-GND-Pad55)") (class "Default")
      (node (ref "*") (pin "55") (pinfunction "GND_55") (pintype "power_in"))
    )
    (net (code "80") (name "unconnected-(*-GNDA-Pad3)") (class "Default")
      (node (ref "*") (pin "3") (pinfunction "GNDA_3") (pintype "power_in"))
    )
    (net (code "81") (name "unconnected-(*-GNDX-Pad35)") (class "Default")
      (node (ref "*") (pin "35") (pinfunction "GNDX_35") (pintype "power_in"))
    )
    (net (code "82") (name "unconnected-(*-OSC0-Pad40)") (class "Default")
      (node (ref "*") (pin "40") (pinfunction "OSC0_40") (pintype "passive"))
    )
    (net (code "83") (name "unconnected-(*-OSC1-Pad41)") (class "Default")
      (node (ref "*") (pin "41") (pinfunction "OSC1_41") (pintype "passive"))
    )
    (net (code "84") (name "unconnected-(*-PC0{slash}TCK{slash}SWCLK-Pad52)") (class "Default")
      (node (ref "*") (pin "52") (pinfunction "PC0/TCK/SWCLK_52") (pintype "bidirectional"))
    )
    (net (code "85") (name "unconnected-(*-PC1{slash}TMS{slash}SWDIO-Pad51)") (class "Default")
      (node (ref "*") (pin "51") (pinfunction "PC1/TMS/SWDIO_51") (pintype "bidirectional"))
    )
    (net (code "86") (name "unconnected-(*-PC2{slash}TDI-Pad50)") (class "Default")
      (node (ref "*") (pin "50") (pinfunction "PC2/TDI_50") (pintype "bidirectional"))
    )
    (net (code "87") (name "unconnected-(*-PC3{slash}TDO{slash}SWO-Pad49)") (class "Default")
      (node (ref "*") (pin "49") (pinfunction "PC3/TDO/SWO_49") (pintype "bidirectional"))
    )
    (net (code "88") (name "unconnected-(*-PC4-Pad16)") (class "Default")
      (node (ref "*") (pin "16") (pinfunction "PC4_16") (pintype "bidirectional"))
    )
    (net (code "89") (name "unconnected-(*-PC5-Pad15)") (class "Default")
      (node (ref "*") (pin "15") (pinfunction "PC5_15") (pintype "bidirectional"))
    )
    (net (code "90") (name "unconnected-(*-PC6-Pad14)") (class "Default")
      (node (ref "*") (pin "14") (pinfunction "PC6_14") (pintype "bidirectional"))
    )
    (net (code "91") (name "unconnected-(*-PC7-Pad13)") (class "Default")
      (node (ref "*") (pin "13") (pinfunction "PC7_13") (pintype "bidirectional"))
    )
    (net (code "92") (name "unconnected-(*-PE0-Pad9)") (class "Default")
      (node (ref "*") (pin "9") (pinfunction "PE0_9") (pintype "bidirectional"))
    )
    (net (code "93") (name "unconnected-(*-PE1-Pad8)") (class "Default")
      (node (ref "*") (pin "8") (pinfunction "PE1_8") (pintype "bidirectional"))
    )
    (net (code "94") (name "unconnected-(*-PE2-Pad7)") (class "Default")
      (node (ref "*") (pin "7") (pinfunction "PE2_7") (pintype "bidirectional"))
    )
    (net (code "95") (name "unconnected-(*-PE3-Pad6)") (class "Default")
      (node (ref "*") (pin "6") (pinfunction "PE3_6") (pintype "bidirectional"))
    )
    (net (code "96") (name "unconnected-(*-PE4-Pad59)") (class "Default")
      (node (ref "*") (pin "59") (pinfunction "PE4_59") (pintype "bidirectional"))
    )
    (net (code "97") (name "unconnected-(*-PE5-Pad60)") (class "Default")
      (node (ref "*") (pin "60") (pinfunction "PE5_60") (pintype "bidirectional"))
    )
    (net (code "98") (name "unconnected-(*-PF0-Pad28)") (class "Default")
      (node (ref "*") (pin "28") (pinfunction "PF0_28") (pintype "bidirectional"))
    )
    (net (code "99") (name "unconnected-(*-PF1-Pad29)") (class "Default")
      (node (ref "*") (pin "29") (pinfunction "PF1_29") (pintype "bidirectional"))
    )
    (net (code "100") (name "unconnected-(*-PF2-Pad30)") (class "Default")
      (node (ref "*") (pin "30") (pinfunction "PF2_30") (pintype "bidirectional"))
    )
    (net (code "101") (name "unconnected-(*-PF3-Pad31)") (class "Default")
      (node (ref "*") (pin "31") (pinfunction "PF3_31") (pintype "bidirectional"))
    )
    (net (code "102") (name "unconnected-(*-PF4-Pad5)") (class "Default")
      (node (ref "*") (pin "5") (pinfunction "PF4_5") (pintype "bidirectional"))
    )
    (net (code "103") (name "unconnected-(*-VBAT-Pad37)") (class "Default")
      (node (ref "*") (pin "37") (pinfunction "VBAT_37") (pintype "passive"))
    )
    (net (code "104") (name "unconnected-(*-VDD-Pad11)") (class "Default")
      (node (ref "*") (pin "11") (pinfunction "VDD_11") (pintype "power_in"))
    )
    (net (code "105") (name "unconnected-(*-VDD-Pad26)") (class "Default")
      (node (ref "*") (pin "26") (pinfunction "VDD_26") (pintype "power_in"))
    )
    (net (code "106") (name "unconnected-(*-VDD-Pad42)") (class "Default")
      (node (ref "*") (pin "42") (pinfunction "VDD_42") (pintype "power_in"))
    )
    (net (code "107") (name "unconnected-(*-VDD-Pad54)") (class "Default")
      (node (ref "*") (pin "54") (pinfunction "VDD_54") (pintype "power_in"))
    )
    (net (code "108") (name "unconnected-(*-VDDA-Pad2)") (class "Default")
      (node (ref "*") (pin "2") (pinfunction "VDDA_2") (pintype "power_in"))
    )
    (net (code "109") (name "unconnected-(*-VDDC-Pad25)") (class "Default")
      (node (ref "*") (pin "25") (pinfunction "VDDC_25") (pintype "power_in"))
    )
    (net (code "110") (name "unconnected-(*-VDDC-Pad56)") (class "Default")
      (node (ref "*") (pin "56") (pinfunction "VDDC_56") (pintype "power_in"))
    )
    (net (code "111") (name "unconnected-(*-XOSC0-Pad34)") (class "Default")
      (node (ref "*") (pin "34") (pinfunction "XOSC0_34") (pintype "passive"))
    )
    (net (code "112") (name "unconnected-(*-XOSC1-Pad36)") (class "Default")
      (node (ref "*") (pin "36") (pinfunction "XOSC1_36") (pintype "passive"))
    )
    (net (code "113") (name "unconnected-(*-~{HIB}-Pad33)") (class "Default")
      (node (ref "*") (pin "33") (pinfunction "~{HIB}_33") (pintype "passive"))
    )
    (net (code "114") (name "unconnected-(*-~{RST}-Pad38)") (class "Default")
      (node (ref "*") (pin "38") (pinfunction "~{RST}_38") (pintype "passive"))
    )
    (net (code "115") (name "unconnected-(*-~{WAKE}-Pad32)") (class "Default")
      (node (ref "*") (pin "32") (pinfunction "~{WAKE}_32") (pintype "passive"))
    )
    (net (code "116") (name "unconnected-(1-NC-Pad1)") (class "Default")
      (node (ref "1") (pin "1") (pinfunction "NC_1") (pintype "passive"))
    )
    (net (code "117") (name "unconnected-(1-NC-Pad8)") (class "Default")
      (node (ref "1") (pin "8") (pinfunction "NC_8") (pintype "passive"))
    )
    (net (code "118") (name "unconnected-(2-NC-Pad1)") (class "Default")
      (node (ref "2") (pin "1") (pinfunction "NC_1") (pintype "passive"))
    )
    (net (code "119") (name "unconnected-(2-NC-Pad8)") (class "Default")
      (node (ref "2") (pin "8") (pinfunction "NC_8") (pintype "passive"))
    )
    (net (code "120") (name "unconnected-(3-NC-Pad1)") (class "Default")
      (node (ref "3") (pin "1") (pinfunction "NC_1") (pintype "passive"))
    )
    (net (code "121") (name "unconnected-(3-NC-Pad8)") (class "Default")
      (node (ref "3") (pin "8") (pinfunction "NC_8") (pintype "passive"))
    )
    (net (code "122") (name "unconnected-(4-NC-Pad1)") (class "Default")
      (node (ref "4") (pin "1") (pinfunction "NC_1") (pintype "passive"))
    )
    (net (code "123") (name "unconnected-(4-NC-Pad8)") (class "Default")
      (node (ref "4") (pin "8") (pinfunction "NC_8") (pintype "passive"))
    )
    (net (code "124") (name "unconnected-(5-NC-Pad1)") (class "Default")
      (node (ref "5") (pin "1") (pinfunction "NC_1") (pintype "passive"))
    )
    (net (code "125") (name "unconnected-(5-NC-Pad8)") (class "Default")
      (node (ref "5") (pin "8") (pinfunction "NC_8") (pintype "passive"))
    )
    (net (code "126") (name "unconnected-(6-NC-Pad1)") (class "Default")
      (node (ref "6") (pin "1") (pinfunction "NC_1") (pintype "passive"))
    )
    (net (code "127") (name "unconnected-(6-NC-Pad8)") (class "Default")
      (node (ref "6") (pin "8") (pinfunction "NC_8") (pintype "passive"))
    )
    (net (code "128") (name "unconnected-(6.1---Padpin-)") (class "Default")
      (node (ref "6.1") (pin "pin-") (pinfunction "-_pin-") (pintype "passive"))
    )
    (net (code "129") (name "unconnected-(6.2---Padpin-)") (class "Default")
      (node (ref "6.2") (pin "pin-") (pinfunction "-_pin-") (pintype "passive"))
    )
    (net (code "130") (name "unconnected-(7-NC-Pad1)") (class "Default")
      (node (ref "7") (pin "1") (pinfunction "NC_1") (pintype "passive"))
    )
    (net (code "131") (name "unconnected-(7-NC-Pad8)") (class "Default")
      (node (ref "7") (pin "8") (pinfunction "NC_8") (pintype "passive"))
    )
    (net (code "132") (name "unconnected-(8-NC-Pad1)") (class "Default")
      (node (ref "8") (pin "1") (pinfunction "NC_1") (pintype "passive"))
    )
    (net (code "133") (name "unconnected-(8-NC-Pad8)") (class "Default")
      (node (ref "8") (pin "8") (pinfunction "NC_8") (pintype "passive"))
    )
    (net (code "134") (name "unconnected-(9-NC-Pad1)") (class "Default")
      (node (ref "9") (pin "1") (pinfunction "NC_1") (pintype "passive"))
    )
    (net (code "135") (name "unconnected-(9-NC-Pad8)") (class "Default")
      (node (ref "9") (pin "8") (pinfunction "NC_8") (pintype "passive"))
    )
    (net (code "136") (name "unconnected-(10-NC-Pad1)") (class "Default")
      (node (ref "10") (pin "1") (pinfunction "NC_1") (pintype "passive"))
    )
    (net (code "137") (name "unconnected-(10-NC-Pad8)") (class "Default")
      (node (ref "10") (pin "8") (pinfunction "NC_8") (pintype "passive"))
    )
    (net (code "138") (name "unconnected-(11-NC-Pad1)") (class "Default")
      (node (ref "11") (pin "1") (pinfunction "NC_1") (pintype "passive"))
    )
    (net (code "139") (name "unconnected-(11-NC-Pad8)") (class "Default")
      (node (ref "11") (pin "8") (pinfunction "NC_8") (pintype "passive"))
    )
    (net (code "140") (name "unconnected-(12-NC-Pad1)") (class "Default")
      (node (ref "12") (pin "1") (pinfunction "NC_1") (pintype "passive"))
    )
    (net (code "141") (name "unconnected-(12-NC-Pad8)") (class "Default")
      (node (ref "12") (pin "8") (pinfunction "NC_8") (pintype "passive"))
    )
    (net (code "142") (name "unconnected-(12.2---Padpin-)") (class "Default")
      (node (ref "12.2") (pin "pin-") (pinfunction "-_pin-") (pintype "passive"))
    )
    (net (code "143") (name "unconnected-(13-NC-Pad1)") (class "Default")
      (node (ref "13") (pin "1") (pinfunction "NC_1") (pintype "passive"))
    )
    (net (code "144") (name "unconnected-(13-NC-Pad8)") (class "Default")
      (node (ref "13") (pin "8") (pinfunction "NC_8") (pintype "passive"))
    )
    (net (code "145") (name "unconnected-(14-NC-Pad1)") (class "Default")
      (node (ref "14") (pin "1") (pinfunction "NC_1") (pintype "passive"))
    )
    (net (code "146") (name "unconnected-(14-NC-Pad8)") (class "Default")
      (node (ref "14") (pin "8") (pinfunction "NC_8") (pintype "passive"))
    )
    (net (code "147") (name "unconnected-(15-NC-Pad1)") (class "Default")
      (node (ref "15") (pin "1") (pinfunction "NC_1") (pintype "passive"))
    )
    (net (code "148") (name "unconnected-(15-NC-Pad8)") (class "Default")
      (node (ref "15") (pin "8") (pinfunction "NC_8") (pintype "passive"))
    )
    (net (code "149") (name "unconnected-(16-NC-Pad1)") (class "Default")
      (node (ref "16") (pin "1") (pinfunction "NC_1") (pintype "passive"))
    )
    (net (code "150") (name "unconnected-(16-NC-Pad8)") (class "Default")
      (node (ref "16") (pin "8") (pinfunction "NC_8") (pintype "passive"))
    )
    (net (code "151") (name "unconnected-(17-NC-Pad1)") (class "Default")
      (node (ref "17") (pin "1") (pinfunction "NC_1") (pintype "passive"))
    )
    (net (code "152") (name "unconnected-(17-NC-Pad8)") (class "Default")
      (node (ref "17") (pin "8") (pinfunction "NC_8") (pintype "passive"))
    )
    (net (code "153") (name "unconnected-(18-NC-Pad1)") (class "Default")
      (node (ref "18") (pin "1") (pinfunction "NC_1") (pintype "passive"))
    )
    (net (code "154") (name "unconnected-(18-NC-Pad8)") (class "Default")
      (node (ref "18") (pin "8") (pinfunction "NC_8") (pintype "passive"))
    )
    (net (code "155") (name "unconnected-(18.1---Padpin-)") (class "Default")
      (node (ref "18.1") (pin "pin-") (pinfunction "-_pin-") (pintype "passive"))
    )
    (net (code "156") (name "unconnected-(18.2---Padpin-)") (class "Default")
      (node (ref "18.2") (pin "pin-") (pinfunction "-_pin-") (pintype "passive"))
    )
    (net (code "157") (name "unconnected-(19-NC-Pad1)") (class "Default")
      (node (ref "19") (pin "1") (pinfunction "NC_1") (pintype "passive"))
    )
    (net (code "158") (name "unconnected-(19-NC-Pad8)") (class "Default")
      (node (ref "19") (pin "8") (pinfunction "NC_8") (pintype "passive"))
    )
    (net (code "159") (name "unconnected-(20-NC-Pad1)") (class "Default")
      (node (ref "20") (pin "1") (pinfunction "NC_1") (pintype "passive"))
    )
    (net (code "160") (name "unconnected-(20-NC-Pad8)") (class "Default")
      (node (ref "20") (pin "8") (pinfunction "NC_8") (pintype "passive"))
    )
    (net (code "161") (name "unconnected-(21-NC-Pad1)") (class "Default")
      (node (ref "21") (pin "1") (pinfunction "NC_1") (pintype "passive"))
    )
    (net (code "162") (name "unconnected-(21-NC-Pad8)") (class "Default")
      (node (ref "21") (pin "8") (pinfunction "NC_8") (pintype "passive"))
    )
    (net (code "163") (name "unconnected-(22-NC-Pad1)") (class "Default")
      (node (ref "22") (pin "1") (pinfunction "NC_1") (pintype "passive"))
    )
    (net (code "164") (name "unconnected-(22-NC-Pad8)") (class "Default")
      (node (ref "22") (pin "8") (pinfunction "NC_8") (pintype "passive"))
    )
    (net (code "165") (name "unconnected-(23-NC-Pad1)") (class "Default")
      (node (ref "23") (pin "1") (pinfunction "NC_1") (pintype "passive"))
    )
    (net (code "166") (name "unconnected-(23-NC-Pad8)") (class "Default")
      (node (ref "23") (pin "8") (pinfunction "NC_8") (pintype "passive"))
    )
    (net (code "167") (name "unconnected-(24-NC-Pad1)") (class "Default")
      (node (ref "24") (pin "1") (pinfunction "NC_1") (pintype "passive"))
    )
    (net (code "168") (name "unconnected-(24-NC-Pad8)") (class "Default")
      (node (ref "24") (pin "8") (pinfunction "NC_8") (pintype "passive"))
    )
    (net (code "169") (name "unconnected-(24.2---Padpin-)") (class "Default")
      (node (ref "24.2") (pin "pin-") (pinfunction "-_pin-") (pintype "passive"))
    )
  )
)
